# PGTN021_octasource_mkiii_panel_b.net
KiCad netlist of a schematic drawn in EAGLE
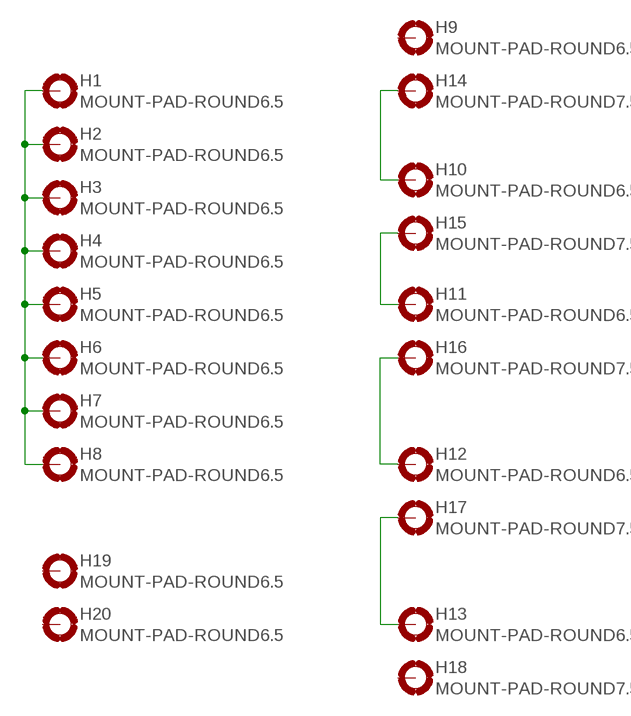
[diagram p0: schematic, sheet 1]

(export (version "E")
  (design (tool "Eeschema 10.0.6"))
  (components
    (comp (ref "H1")
      (value "MOUNT-PAD-ROUND6.5")
      (footprint "eagle-import:6.5-PAD")
      (libsource (lib "eagle-import") (part "MOUNT-PAD-ROUND6.5"))
    )
    (comp (ref "H2")
      (value "MOUNT-PAD-ROUND6.5")
      (footprint "eagle-import:6.5-PAD")
      (libsource (lib "eagle-import") (part "MOUNT-PAD-ROUND6.5"))
    )
    (comp (ref "H3")
      (value "MOUNT-PAD-ROUND6.5")
      (footprint "eagle-import:6.5-PAD")
      (libsource (lib "eagle-import") (part "MOUNT-PAD-ROUND6.5"))
    )
    (comp (ref "H4")
      (value "MOUNT-PAD-ROUND6.5")
      (footprint "eagle-import:6.5-PAD")
      (libsource (lib "eagle-import") (part "MOUNT-PAD-ROUND6.5"))
    )
    (comp (ref "H5")
      (value "MOUNT-PAD-ROUND6.5")
      (footprint "eagle-import:6.5-PAD")
      (libsource (lib "eagle-import") (part "MOUNT-PAD-ROUND6.5"))
    )
    (comp (ref "H6")
      (value "MOUNT-PAD-ROUND6.5")
      (footprint "eagle-import:6.5-PAD")
      (libsource (lib "eagle-import") (part "MOUNT-PAD-ROUND6.5"))
    )
    (comp (ref "H7")
      (value "MOUNT-PAD-ROUND6.5")
      (footprint "eagle-import:6.5-PAD")
      (libsource (lib "eagle-import") (part "MOUNT-PAD-ROUND6.5"))
    )
    (comp (ref "H8")
      (value "MOUNT-PAD-ROUND6.5")
      (footprint "eagle-import:6.5-PAD")
      (libsource (lib "eagle-import") (part "MOUNT-PAD-ROUND6.5"))
    )
    (comp (ref "H9")
      (value "MOUNT-PAD-ROUND6.5")
      (footprint "eagle-import:6.5-PAD")
      (libsource (lib "eagle-import") (part "MOUNT-PAD-ROUND6.5"))
    )
    (comp (ref "H10")
      (value "MOUNT-PAD-ROUND6.5")
      (footprint "eagle-import:6.5-PAD")
      (libsource (lib "eagle-import") (part "MOUNT-PAD-ROUND6.5"))
    )
    (comp (ref "H11")
      (value "MOUNT-PAD-ROUND6.5")
      (footprint "eagle-import:6.5-PAD")
      (libsource (lib "eagle-import") (part "MOUNT-PAD-ROUND6.5"))
    )
    (comp (ref "H12")
      (value "MOUNT-PAD-ROUND6.5")
      (footprint "eagle-import:6.5-PAD")
      (libsource (lib "eagle-import") (part "MOUNT-PAD-ROUND6.5"))
    )
    (comp (ref "H13")
      (value "MOUNT-PAD-ROUND6.5")
      (footprint "eagle-import:6.5-PAD")
      (libsource (lib "eagle-import") (part "MOUNT-PAD-ROUND6.5"))
    )
    (comp (ref "H14")
      (value "MOUNT-PAD-ROUND7.5")
      (footprint "eagle-import:7.5-PAD")
      (libsource (lib "eagle-import") (part "MOUNT-PAD-ROUND7.5"))
    )
    (comp (ref "H15")
      (value "MOUNT-PAD-ROUND7.5")
      (footprint "eagle-import:7.5-PAD")
      (libsource (lib "eagle-import") (part "MOUNT-PAD-ROUND7.5"))
    )
    (comp (ref "H16")
      (value "MOUNT-PAD-ROUND7.5")
      (footprint "eagle-import:7.5-PAD")
      (libsource (lib "eagle-import") (part "MOUNT-PAD-ROUND7.5"))
    )
    (comp (ref "H17")
      (value "MOUNT-PAD-ROUND7.5")
      (footprint "eagle-import:7.5-PAD")
      (libsource (lib "eagle-import") (part "MOUNT-PAD-ROUND7.5"))
    )
    (comp (ref "H18")
      (value "MOUNT-PAD-ROUND7.5")
      (footprint "eagle-import:7.5-PAD")
      (libsource (lib "eagle-import") (part "MOUNT-PAD-ROUND7.5"))
    )
    (comp (ref "H19")
      (value "MOUNT-PAD-ROUND6.5")
      (footprint "eagle-import:6.5-PAD")
      (libsource (lib "eagle-import") (part "MOUNT-PAD-ROUND6.5"))
    )
    (comp (ref "H20")
      (value "MOUNT-PAD-ROUND6.5")
      (footprint "eagle-import:6.5-PAD")
      (libsource (lib "eagle-import") (part "MOUNT-PAD-ROUND6.5"))
    )
  )
  (nets
    (net (code "1") (name "Net-(H1-MOUNT)") (class "Default")
      (node (ref "H1") (pin "B6.5") (pinfunction "MOUNT_B6.5") (pintype "passive"))
      (node (ref "H2") (pin "B6.5") (pinfunction "MOUNT_B6.5") (pintype "passive"))
      (node (ref "H3") (pin "B6.5") (pinfunction "MOUNT_B6.5") (pintype "passive"))
      (node (ref "H4") (pin "B6.5") (pinfunction "MOUNT_B6.5") (pintype "passive"))
      (node (ref "H5") (pin "B6.5") (pinfunction "MOUNT_B6.5") (pintype "passive"))
      (node (ref "H6") (pin "B6.5") (pinfunction "MOUNT_B6.5") (pintype "passive"))
      (node (ref "H7") (pin "B6.5") (pinfunction "MOUNT_B6.5") (pintype "passive"))
      (node (ref "H8") (pin "B6.5") (pinfunction "MOUNT_B6.5") (pintype "passive"))
    )
    (net (code "2") (name "Net-(H10-MOUNT)") (class "Default")
      (node (ref "H10") (pin "B6.5") (pinfunction "MOUNT_B6.5") (pintype "passive"))
      (node (ref "H14") (pin "B7.5") (pinfunction "MOUNT_B7.5") (pintype "passive"))
    )
    (net (code "3") (name "Net-(H11-MOUNT)") (class "Default")
      (node (ref "H11") (pin "B6.5") (pinfunction "MOUNT_B6.5") (pintype "passive"))
      (node (ref "H15") (pin "B7.5") (pinfunction "MOUNT_B7.5") (pintype "passive"))
    )
    (net (code "4") (name "Net-(H12-MOUNT)") (class "Default")
      (node (ref "H12") (pin "B6.5") (pinfunction "MOUNT_B6.5") (pintype "passive"))
      (node (ref "H16") (pin "B7.5") (pinfunction "MOUNT_B7.5") (pintype "passive"))
    )
    (net (code "5") (name "Net-(H13-MOUNT)") (class "Default")
      (node (ref "H13") (pin "B6.5") (pinfunction "MOUNT_B6.5") (pintype "passive"))
      (node (ref "H17") (pin "B7.5") (pinfunction "MOUNT_B7.5") (pintype "passive"))
    )
    (net (code "6") (name "unconnected-(H9-MOUNT-PadB6.5)") (class "Default")
      (node (ref "H9") (pin "B6.5") (pinfunction "MOUNT_B6.5") (pintype "passive"))
    )
    (net (code "7") (name "unconnected-(H18-MOUNT-PadB7.5)") (class "Default")
      (node (ref "H18") (pin "B7.5") (pinfunction "MOUNT_B7.5") (pintype "passive"))
    )
    (net (code "8") (name "unconnected-(H19-MOUNT-PadB6.5)") (class "Default")
      (node (ref "H19") (pin "B6.5") (pinfunction "MOUNT_B6.5") (pintype "passive"))
    )
    (net (code "9") (name "unconnected-(H20-MOUNT-PadB6.5)") (class "Default")
      (node (ref "H20") (pin "B6.5") (pinfunction "MOUNT_B6.5") (pintype "passive"))
    )
  )
)
